# OhEyeZero.net
KiCad netlist of a schematic drawn in EAGLE
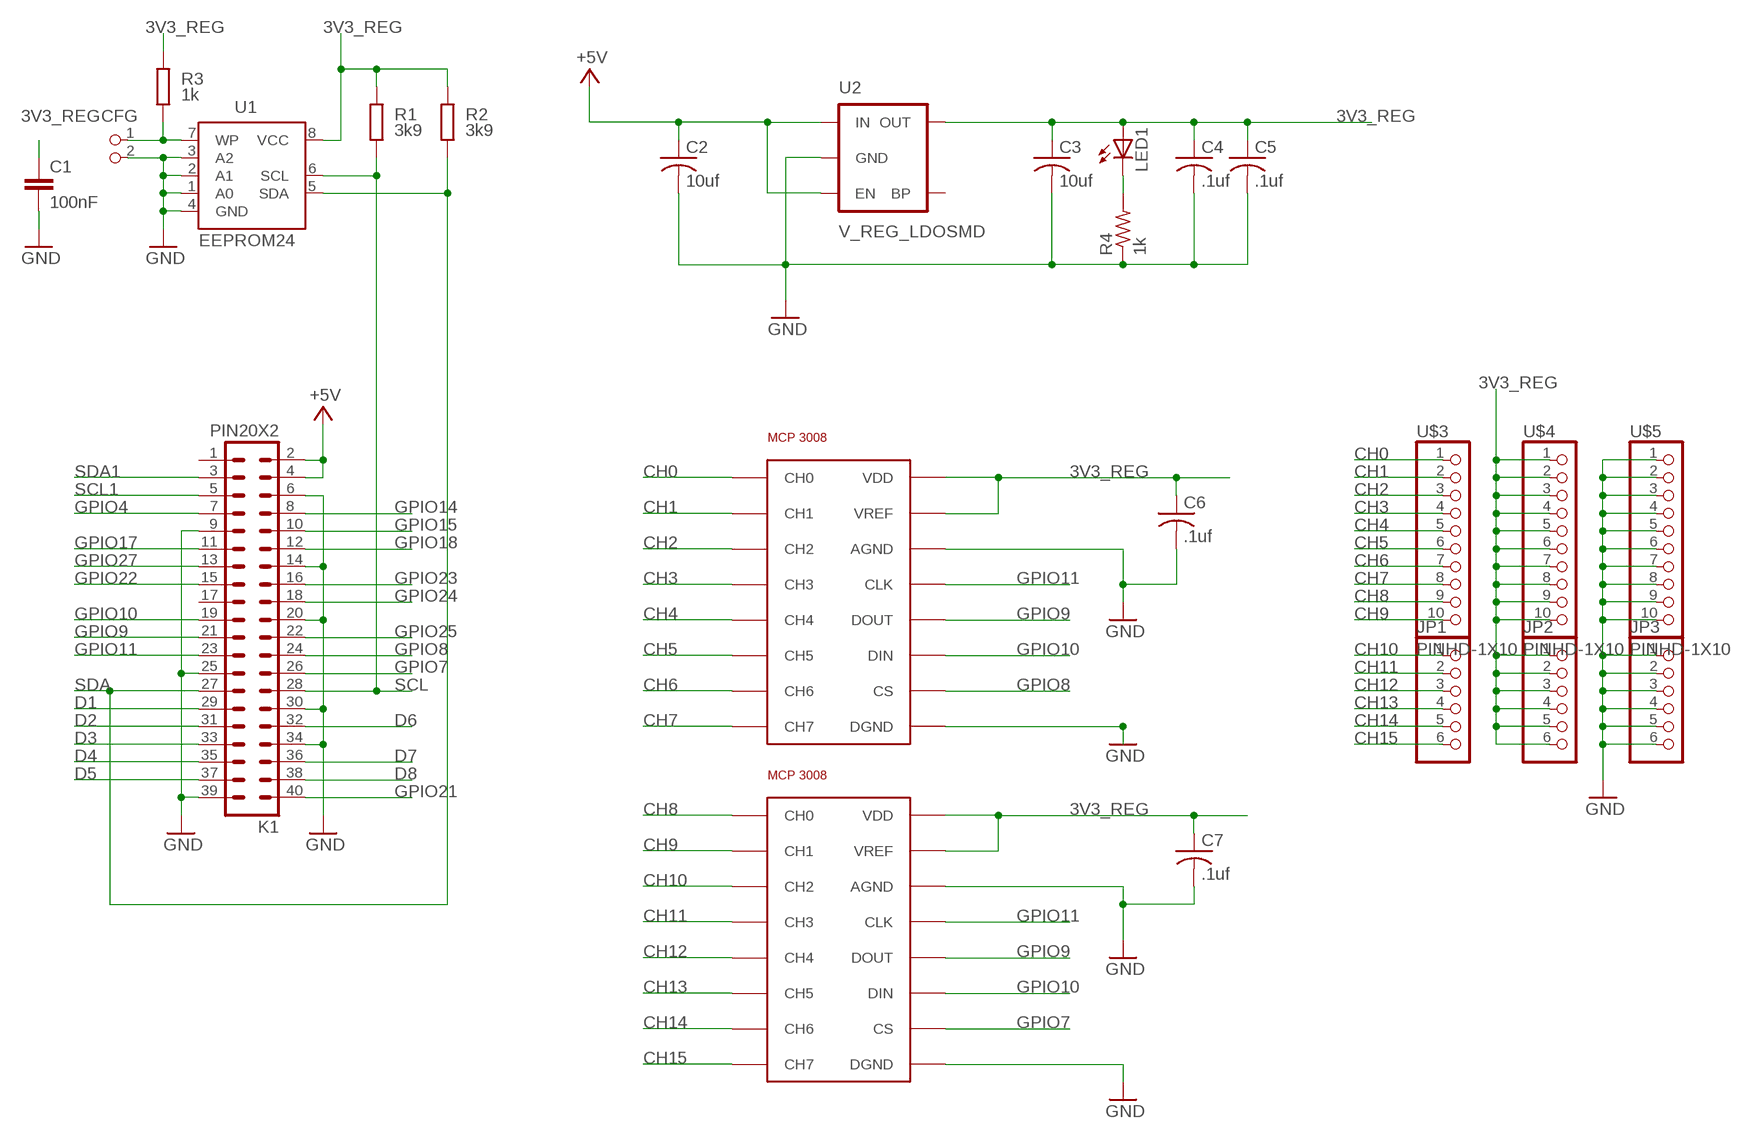
[diagram p0: schematic, sheet 1]

(export (version "E")
  (design (tool "Eeschema 10.0.6"))
  (components
    (comp (ref "C1")
      (value "100nF")
      (footprint "eagle-import:C0805K")
      (libsource (lib "eagle-import") (part "C-EUC0805K"))
    )
    (comp (ref "C2")
      (value "10uf")
      (footprint "eagle-import:C0805K")
      (libsource (lib "eagle-import") (part "C-USC0805K"))
    )
    (comp (ref "C3")
      (value "10uf")
      (footprint "eagle-import:C0805K")
      (libsource (lib "eagle-import") (part "C-USC0805K"))
    )
    (comp (ref "C4")
      (value ".1uf")
      (footprint "eagle-import:C0805K")
      (libsource (lib "eagle-import") (part "C-USC0805K"))
    )
    (comp (ref "C5")
      (value ".1uf")
      (footprint "eagle-import:C0805K")
      (libsource (lib "eagle-import") (part "C-USC0805K"))
    )
    (comp (ref "C6")
      (value ".1uf")
      (footprint "eagle-import:C0805K")
      (libsource (lib "eagle-import") (part "C-USC0805K"))
    )
    (comp (ref "C7")
      (value ".1uf")
      (footprint "eagle-import:C0805K")
      (libsource (lib "eagle-import") (part "C-USC0805K"))
    )
    (comp (ref "CFG")
      (value "PIN2_100")
      (footprint "eagle-import:PIN_W_2")
      (libsource (lib "eagle-import") (part "PIN2_100"))
    )
    (comp (ref "JP1")
      (value "PINHD-1X6B")
      (footprint "eagle-import:1X06-BIG")
      (libsource (lib "eagle-import") (part "PINHD-1X6B"))
    )
    (comp (ref "JP2")
      (value "PINHD-1X6B")
      (footprint "eagle-import:1X06-BIG")
      (libsource (lib "eagle-import") (part "PINHD-1X6B"))
    )
    (comp (ref "JP3")
      (value "PINHD-1X6B")
      (footprint "eagle-import:1X06-BIG")
      (libsource (lib "eagle-import") (part "PINHD-1X6B"))
    )
    (comp (ref "K1")
      (value "PIN20X2")
      (footprint "eagle-import:PIN_20X2")
      (libsource (lib "eagle-import") (part "PIN20X2"))
    )
    (comp (ref "LED1")
      (value "LEDLED-0805")
      (footprint "eagle-import:LED0805.PAC")
      (libsource (lib "eagle-import") (part "LEDLED-0805"))
    )
    (comp (ref "R1")
      (value "3k9")
      (footprint "eagle-import:M0805")
      (fields (field (name "TOLERANCE") "5%"))
      (libsource (lib "eagle-import") (part "R-EU_M0805"))
    )
    (comp (ref "R2")
      (value "3k9")
      (footprint "eagle-import:M0805")
      (fields (field (name "TOLERANCE") "5%"))
      (libsource (lib "eagle-import") (part "R-EU_M0805"))
    )
    (comp (ref "R3")
      (value "1k")
      (footprint "eagle-import:M0805")
      (fields (field (name "TOLERANCE") "5%"))
      (libsource (lib "eagle-import") (part "R-EU_M0805"))
    )
    (comp (ref "R4")
      (value "1k")
      (footprint "eagle-import:R0805W")
      (libsource (lib "eagle-import") (part "R-US_R0805W"))
    )
    (comp (ref "U$1")
      (value "MCP3008_ADC")
      (footprint "eagle-import:SOIC16")
      (libsource (lib "eagle-import") (part "MCP3008_ADC"))
    )
    (comp (ref "U$2")
      (value "MCP3008_ADC")
      (footprint "eagle-import:SOIC16")
      (libsource (lib "eagle-import") (part "MCP3008_ADC"))
    )
    (comp (ref "U$3")
      (value "PINHD-1X10")
      (footprint "eagle-import:1X10-BIG")
      (libsource (lib "eagle-import") (part "PINHD-1X10"))
    )
    (comp (ref "U$4")
      (value "PINHD-1X10")
      (footprint "eagle-import:1X10-BIG")
      (libsource (lib "eagle-import") (part "PINHD-1X10"))
    )
    (comp (ref "U$5")
      (value "PINHD-1X10")
      (footprint "eagle-import:1X10-BIG")
      (libsource (lib "eagle-import") (part "PINHD-1X10"))
    )
    (comp (ref "U1")
      (value "EEPROM24")
      (footprint "eagle-import:SOIC8")
      (libsource (lib "eagle-import") (part "EEPROM24"))
    )
    (comp (ref "U2")
      (value "V_REG_LDOSMD")
      (footprint "eagle-import:SOT23-5")
      (libsource (lib "eagle-import") (part "V_REG_LDOSMD"))
    )
  )
  (nets
    (net (code "1") (name "+5V") (class "Default")
      (node (ref "C2") (pin "1") (pinfunction "1_1") (pintype "passive"))
      (node (ref "K1") (pin "2") (pinfunction "2_2") (pintype "passive"))
      (node (ref "K1") (pin "4") (pinfunction "4_4") (pintype "passive"))
      (node (ref "U2") (pin "1") (pinfunction "IN_1") (pintype "input"))
      (node (ref "U2") (pin "3") (pinfunction "EN_3") (pintype "input"))
    )
    (net (code "2") (name "/3V3_REG") (class "Default")
      (node (ref "C1") (pin "1") (pinfunction "1_1") (pintype "passive"))
      (node (ref "C3") (pin "1") (pinfunction "1_1") (pintype "passive"))
      (node (ref "C4") (pin "1") (pinfunction "1_1") (pintype "passive"))
      (node (ref "C5") (pin "1") (pinfunction "1_1") (pintype "passive"))
      (node (ref "C6") (pin "1") (pinfunction "1_1") (pintype "passive"))
      (node (ref "C7") (pin "1") (pinfunction "1_1") (pintype "passive"))
      (node (ref "JP2") (pin "1") (pinfunction "1_1") (pintype "passive"))
      (node (ref "JP2") (pin "2") (pinfunction "2_2") (pintype "passive"))
      (node (ref "JP2") (pin "3") (pinfunction "3_3") (pintype "passive"))
      (node (ref "JP2") (pin "4") (pinfunction "4_4") (pintype "passive"))
      (node (ref "JP2") (pin "5") (pinfunction "5_5") (pintype "passive"))
      (node (ref "JP2") (pin "6") (pinfunction "6_6") (pintype "passive"))
      (node (ref "LED1") (pin "A") (pinfunction "A_A") (pintype "passive"))
      (node (ref "R1") (pin "2") (pinfunction "2_2") (pintype "passive"))
      (node (ref "R2") (pin "2") (pinfunction "2_2") (pintype "passive"))
      (node (ref "R3") (pin "2") (pinfunction "2_2") (pintype "passive"))
      (node (ref "U$1") (pin "P$15") (pinfunction "VREF_P$15") (pintype "bidirectional"))
      (node (ref "U$1") (pin "P$16") (pinfunction "VDD_P$16") (pintype "bidirectional"))
      (node (ref "U$2") (pin "P$15") (pinfunction "VREF_P$15") (pintype "bidirectional"))
      (node (ref "U$2") (pin "P$16") (pinfunction "VDD_P$16") (pintype "bidirectional"))
      (node (ref "U$4") (pin "1") (pinfunction "1_1") (pintype "passive"))
      (node (ref "U$4") (pin "10") (pinfunction "10_10") (pintype "passive"))
      (node (ref "U$4") (pin "2") (pinfunction "2_2") (pintype "passive"))
      (node (ref "U$4") (pin "3") (pinfunction "3_3") (pintype "passive"))
      (node (ref "U$4") (pin "4") (pinfunction "4_4") (pintype "passive"))
      (node (ref "U$4") (pin "5") (pinfunction "5_5") (pintype "passive"))
      (node (ref "U$4") (pin "6") (pinfunction "6_6") (pintype "passive"))
      (node (ref "U$4") (pin "7") (pinfunction "7_7") (pintype "passive"))
      (node (ref "U$4") (pin "8") (pinfunction "8_8") (pintype "passive"))
      (node (ref "U$4") (pin "9") (pinfunction "9_9") (pintype "passive"))
      (node (ref "U1") (pin "8") (pinfunction "VCC_8") (pintype "power_in"))
      (node (ref "U2") (pin "5") (pinfunction "OUT_5") (pintype "passive"))
    )
    (net (code "3") (name "/CH0") (class "Default")
      (node (ref "U$1") (pin "P$1") (pinfunction "CH0_P$1") (pintype "bidirectional"))
      (node (ref "U$3") (pin "1") (pinfunction "1_1") (pintype "passive"))
    )
    (net (code "4") (name "/CH1") (class "Default")
      (node (ref "U$1") (pin "P$2") (pinfunction "CH1_P$2") (pintype "bidirectional"))
      (node (ref "U$3") (pin "2") (pinfunction "2_2") (pintype "passive"))
    )
    (net (code "5") (name "/CH2") (class "Default")
      (node (ref "U$1") (pin "P$3") (pinfunction "CH2_P$3") (pintype "bidirectional"))
      (node (ref "U$3") (pin "3") (pinfunction "3_3") (pintype "passive"))
    )
    (net (code "6") (name "/CH3") (class "Default")
      (node (ref "U$1") (pin "P$4") (pinfunction "CH3_P$4") (pintype "bidirectional"))
      (node (ref "U$3") (pin "4") (pinfunction "4_4") (pintype "passive"))
    )
    (net (code "7") (name "/CH4") (class "Default")
      (node (ref "U$1") (pin "P$5") (pinfunction "CH4_P$5") (pintype "bidirectional"))
      (node (ref "U$3") (pin "5") (pinfunction "5_5") (pintype "passive"))
    )
    (net (code "8") (name "/CH5") (class "Default")
      (node (ref "U$1") (pin "P$6") (pinfunction "CH5_P$6") (pintype "bidirectional"))
      (node (ref "U$3") (pin "6") (pinfunction "6_6") (pintype "passive"))
    )
    (net (code "9") (name "/CH6") (class "Default")
      (node (ref "U$1") (pin "P$7") (pinfunction "CH6_P$7") (pintype "bidirectional"))
      (node (ref "U$3") (pin "7") (pinfunction "7_7") (pintype "passive"))
    )
    (net (code "10") (name "/CH7") (class "Default")
      (node (ref "U$1") (pin "P$8") (pinfunction "CH7_P$8") (pintype "bidirectional"))
      (node (ref "U$3") (pin "8") (pinfunction "8_8") (pintype "passive"))
    )
    (net (code "11") (name "/CH8") (class "Default")
      (node (ref "U$2") (pin "P$1") (pinfunction "CH0_P$1") (pintype "bidirectional"))
      (node (ref "U$3") (pin "9") (pinfunction "9_9") (pintype "passive"))
    )
    (net (code "12") (name "/CH9") (class "Default")
      (node (ref "U$2") (pin "P$2") (pinfunction "CH1_P$2") (pintype "bidirectional"))
      (node (ref "U$3") (pin "10") (pinfunction "10_10") (pintype "passive"))
    )
    (net (code "13") (name "/CH10") (class "Default")
      (node (ref "JP1") (pin "1") (pinfunction "1_1") (pintype "passive"))
      (node (ref "U$2") (pin "P$3") (pinfunction "CH2_P$3") (pintype "bidirectional"))
    )
    (net (code "14") (name "/CH11") (class "Default")
      (node (ref "JP1") (pin "2") (pinfunction "2_2") (pintype "passive"))
      (node (ref "U$2") (pin "P$4") (pinfunction "CH3_P$4") (pintype "bidirectional"))
    )
    (net (code "15") (name "/CH12") (class "Default")
      (node (ref "JP1") (pin "3") (pinfunction "3_3") (pintype "passive"))
      (node (ref "U$2") (pin "P$5") (pinfunction "CH4_P$5") (pintype "bidirectional"))
    )
    (net (code "16") (name "/CH13") (class "Default")
      (node (ref "JP1") (pin "4") (pinfunction "4_4") (pintype "passive"))
      (node (ref "U$2") (pin "P$6") (pinfunction "CH5_P$6") (pintype "bidirectional"))
    )
    (net (code "17") (name "/CH14") (class "Default")
      (node (ref "JP1") (pin "5") (pinfunction "5_5") (pintype "passive"))
      (node (ref "U$2") (pin "P$7") (pinfunction "CH6_P$7") (pintype "bidirectional"))
    )
    (net (code "18") (name "/CH15") (class "Default")
      (node (ref "JP1") (pin "6") (pinfunction "6_6") (pintype "passive"))
      (node (ref "U$2") (pin "P$8") (pinfunction "CH7_P$8") (pintype "bidirectional"))
    )
    (net (code "19") (name "/D1") (class "Default")
      (node (ref "K1") (pin "29") (pinfunction "29_29") (pintype "passive"))
    )
    (net (code "20") (name "/D2") (class "Default")
      (node (ref "K1") (pin "31") (pinfunction "31_31") (pintype "passive"))
    )
    (net (code "21") (name "/D3") (class "Default")
      (node (ref "K1") (pin "33") (pinfunction "33_33") (pintype "passive"))
    )
    (net (code "22") (name "/D4") (class "Default")
      (node (ref "K1") (pin "35") (pinfunction "35_35") (pintype "passive"))
    )
    (net (code "23") (name "/D5") (class "Default")
      (node (ref "K1") (pin "37") (pinfunction "37_37") (pintype "passive"))
    )
    (net (code "24") (name "/D6") (class "Default")
      (node (ref "K1") (pin "32") (pinfunction "32_32") (pintype "passive"))
    )
    (net (code "25") (name "/D7") (class "Default")
      (node (ref "K1") (pin "36") (pinfunction "36_36") (pintype "passive"))
    )
    (net (code "26") (name "/D8") (class "Default")
      (node (ref "K1") (pin "38") (pinfunction "38_38") (pintype "passive"))
    )
    (net (code "27") (name "/GPIO4") (class "Default")
      (node (ref "K1") (pin "7") (pinfunction "7_7") (pintype "passive"))
    )
    (net (code "28") (name "/GPIO7") (class "Default")
      (node (ref "K1") (pin "26") (pinfunction "26_26") (pintype "passive"))
      (node (ref "U$2") (pin "P$10") (pinfunction "CS_P$10") (pintype "bidirectional"))
    )
    (net (code "29") (name "/GPIO8") (class "Default")
      (node (ref "K1") (pin "24") (pinfunction "24_24") (pintype "passive"))
      (node (ref "U$1") (pin "P$10") (pinfunction "CS_P$10") (pintype "bidirectional"))
    )
    (net (code "30") (name "/GPIO9") (class "Default")
      (node (ref "K1") (pin "21") (pinfunction "21_21") (pintype "passive"))
      (node (ref "U$1") (pin "P$12") (pinfunction "DOUT_P$12") (pintype "bidirectional"))
      (node (ref "U$2") (pin "P$12") (pinfunction "DOUT_P$12") (pintype "bidirectional"))
    )
    (net (code "31") (name "/GPIO10") (class "Default")
      (node (ref "K1") (pin "19") (pinfunction "19_19") (pintype "passive"))
      (node (ref "U$1") (pin "P$11") (pinfunction "DIN_P$11") (pintype "bidirectional"))
      (node (ref "U$2") (pin "P$11") (pinfunction "DIN_P$11") (pintype "bidirectional"))
    )
    (net (code "32") (name "/GPIO11") (class "Default")
      (node (ref "K1") (pin "23") (pinfunction "23_23") (pintype "passive"))
      (node (ref "U$1") (pin "P$13") (pinfunction "CLK_P$13") (pintype "bidirectional"))
      (node (ref "U$2") (pin "P$13") (pinfunction "CLK_P$13") (pintype "bidirectional"))
    )
    (net (code "33") (name "/GPIO14") (class "Default")
      (node (ref "K1") (pin "8") (pinfunction "8_8") (pintype "passive"))
    )
    (net (code "34") (name "/GPIO15") (class "Default")
      (node (ref "K1") (pin "10") (pinfunction "10_10") (pintype "passive"))
    )
    (net (code "35") (name "/GPIO17") (class "Default")
      (node (ref "K1") (pin "11") (pinfunction "11_11") (pintype "passive"))
    )
    (net (code "36") (name "/GPIO18") (class "Default")
      (node (ref "K1") (pin "12") (pinfunction "12_12") (pintype "passive"))
    )
    (net (code "37") (name "/GPIO21") (class "Default")
      (node (ref "K1") (pin "40") (pinfunction "40_40") (pintype "passive"))
    )
    (net (code "38") (name "/GPIO22") (class "Default")
      (node (ref "K1") (pin "15") (pinfunction "15_15") (pintype "passive"))
    )
    (net (code "39") (name "/GPIO23") (class "Default")
      (node (ref "K1") (pin "16") (pinfunction "16_16") (pintype "passive"))
    )
    (net (code "40") (name "/GPIO24") (class "Default")
      (node (ref "K1") (pin "18") (pinfunction "18_18") (pintype "passive"))
    )
    (net (code "41") (name "/GPIO25") (class "Default")
      (node (ref "K1") (pin "22") (pinfunction "22_22") (pintype "passive"))
    )
    (net (code "42") (name "/GPIO27") (class "Default")
      (node (ref "K1") (pin "13") (pinfunction "13_13") (pintype "passive"))
    )
    (net (code "43") (name "/SCL") (class "Default")
      (node (ref "K1") (pin "28") (pinfunction "28_28") (pintype "passive"))
      (node (ref "R1") (pin "1") (pinfunction "1_1") (pintype "passive"))
      (node (ref "U1") (pin "6") (pinfunction "SCL_6") (pintype "input"))
    )
    (net (code "44") (name "/SCL1") (class "Default")
      (node (ref "K1") (pin "5") (pinfunction "5_5") (pintype "passive"))
    )
    (net (code "45") (name "/SDA") (class "Default")
      (node (ref "K1") (pin "27") (pinfunction "27_27") (pintype "passive"))
      (node (ref "R2") (pin "1") (pinfunction "1_1") (pintype "passive"))
      (node (ref "U1") (pin "5") (pinfunction "SDA_5") (pintype "bidirectional"))
    )
    (net (code "46") (name "/SDA1") (class "Default")
      (node (ref "K1") (pin "3") (pinfunction "3_3") (pintype "passive"))
    )
    (net (code "47") (name "GND") (class "Default")
      (node (ref "C1") (pin "2") (pinfunction "2_2") (pintype "passive"))
      (node (ref "C2") (pin "2") (pinfunction "2_2") (pintype "passive"))
      (node (ref "C3") (pin "2") (pinfunction "2_2") (pintype "passive"))
      (node (ref "C4") (pin "2") (pinfunction "2_2") (pintype "passive"))
      (node (ref "C5") (pin "2") (pinfunction "2_2") (pintype "passive"))
      (node (ref "C6") (pin "2") (pinfunction "2_2") (pintype "passive"))
      (node (ref "C7") (pin "2") (pinfunction "2_2") (pintype "passive"))
      (node (ref "CFG") (pin "2") (pinfunction "2_2") (pintype "passive"))
      (node (ref "JP3") (pin "1") (pinfunction "1_1") (pintype "passive"))
      (node (ref "JP3") (pin "2") (pinfunction "2_2") (pintype "passive"))
      (node (ref "JP3") (pin "3") (pinfunction "3_3") (pintype "passive"))
      (node (ref "JP3") (pin "4") (pinfunction "4_4") (pintype "passive"))
      (node (ref "JP3") (pin "5") (pinfunction "5_5") (pintype "passive"))
      (node (ref "JP3") (pin "6") (pinfunction "6_6") (pintype "passive"))
      (node (ref "K1") (pin "14") (pinfunction "14_14") (pintype "passive"))
      (node (ref "K1") (pin "20") (pinfunction "20_20") (pintype "passive"))
      (node (ref "K1") (pin "25") (pinfunction "25_25") (pintype "passive"))
      (node (ref "K1") (pin "30") (pinfunction "30_30") (pintype "passive"))
      (node (ref "K1") (pin "34") (pinfunction "34_34") (pintype "passive"))
      (node (ref "K1") (pin "39") (pinfunction "39_39") (pintype "passive"))
      (node (ref "K1") (pin "6") (pinfunction "6_6") (pintype "passive"))
      (node (ref "K1") (pin "9") (pinfunction "9_9") (pintype "passive"))
      (node (ref "R4") (pin "1") (pinfunction "1_1") (pintype "passive"))
      (node (ref "U$1") (pin "P$14") (pinfunction "AGND_P$14") (pintype "bidirectional"))
      (node (ref "U$1") (pin "P$9") (pinfunction "DGND_P$9") (pintype "bidirectional"))
      (node (ref "U$2") (pin "P$14") (pinfunction "AGND_P$14") (pintype "bidirectional"))
      (node (ref "U$2") (pin "P$9") (pinfunction "DGND_P$9") (pintype "bidirectional"))
      (node (ref "U$5") (pin "1") (pinfunction "1_1") (pintype "passive"))
      (node (ref "U$5") (pin "10") (pinfunction "10_10") (pintype "passive"))
      (node (ref "U$5") (pin "2") (pinfunction "2_2") (pintype "passive"))
      (node (ref "U$5") (pin "3") (pinfunction "3_3") (pintype "passive"))
      (node (ref "U$5") (pin "4") (pinfunction "4_4") (pintype "passive"))
      (node (ref "U$5") (pin "5") (pinfunction "5_5") (pintype "passive"))
      (node (ref "U$5") (pin "6") (pinfunction "6_6") (pintype "passive"))
      (node (ref "U$5") (pin "7") (pinfunction "7_7") (pintype "passive"))
      (node (ref "U$5") (pin "8") (pinfunction "8_8") (pintype "passive"))
      (node (ref "U$5") (pin "9") (pinfunction "9_9") (pintype "passive"))
      (node (ref "U1") (pin "1") (pinfunction "A0_1") (pintype "input"))
      (node (ref "U1") (pin "2") (pinfunction "A1_2") (pintype "input"))
      (node (ref "U1") (pin "3") (pinfunction "A2_3") (pintype "input"))
      (node (ref "U1") (pin "4") (pinfunction "GND_4") (pintype "power_in"))
      (node (ref "U2") (pin "2") (pinfunction "GND_2") (pintype "input"))
    )
    (net (code "48") (name "Net-(LED1-C)") (class "Default")
      (node (ref "LED1") (pin "K") (pinfunction "C_K") (pintype "passive"))
      (node (ref "R4") (pin "2") (pinfunction "2_2") (pintype "passive"))
    )
    (net (code "49") (name "Net-(U1-WP)") (class "Default")
      (node (ref "CFG") (pin "1") (pinfunction "1_1") (pintype "passive"))
      (node (ref "R3") (pin "1") (pinfunction "1_1") (pintype "passive"))
      (node (ref "U1") (pin "7") (pinfunction "WP_7") (pintype "input"))
    )
    (net (code "50") (name "unconnected-(K1-Pad1)") (class "Default")
      (node (ref "K1") (pin "1") (pinfunction "1_1") (pintype "passive"))
    )
    (net (code "51") (name "unconnected-(K1-Pad17)") (class "Default")
      (node (ref "K1") (pin "17") (pinfunction "17_17") (pintype "passive"))
    )
    (net (code "52") (name "unconnected-(U2-BP-Pad4)") (class "Default")
      (node (ref "U2") (pin "4") (pinfunction "BP_4") (pintype "input"))
    )
  )
)
